# joystick-DAC-GPS.net
KiCad netlist of a schematic drawn in EAGLE
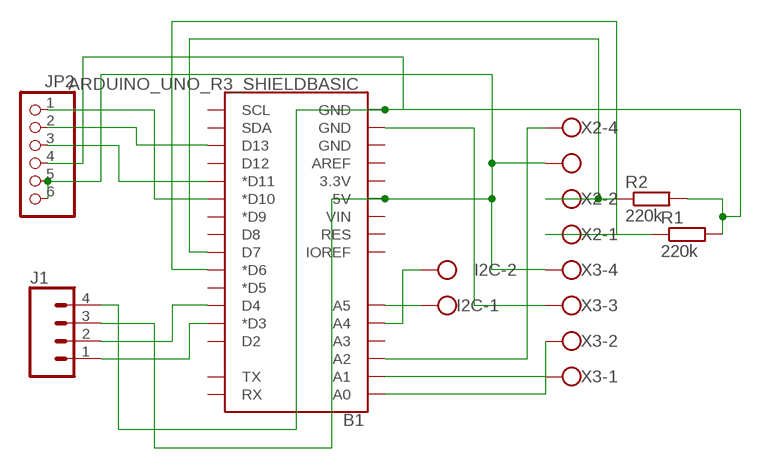
[diagram p0: schematic, sheet 1]

(export (version "E")
  (design (tool "Eeschema 10.0.6"))
  (components
    (comp (ref "B1")
      (value "ARDUINO_UNO_R3_SHIELDBASIC")
      (footprint "eagle-import:UNO_R3_SHIELD")
      (libsource (lib "eagle-import") (part "ARDUINO_UNO_R3_SHIELDBASIC"))
    )
    (comp (ref "I2C")
      (value "W237-102")
      (footprint "eagle-import:W237-102")
      (fields (field (name "MPN") "237-102"))
      (libsource (lib "eagle-import") (part "W237-102"))
    )
    (comp (ref "J1")
      (value "CONN_04")
      (footprint "eagle-import:1X04")
      (libsource (lib "eagle-import") (part "CONN_04"))
    )
    (comp (ref "JP2")
      (value "PINHD-1X6")
      (footprint "eagle-import:1X06")
      (libsource (lib "eagle-import") (part "PINHD-1X6"))
    )
    (comp (ref "R1")
      (value "220k")
      (footprint "eagle-import:0204_7")
      (libsource (lib "eagle-import") (part "R-EU_0204/7"))
    )
    (comp (ref "R2")
      (value "220k")
      (footprint "eagle-import:0204_7")
      (libsource (lib "eagle-import") (part "R-EU_0204/7"))
    )
    (comp (ref "X2")
      (value "W237-4")
      (footprint "eagle-import:W237-4")
      (libsource (lib "eagle-import") (part "W237-4"))
    )
    (comp (ref "X3")
      (value "W237-4")
      (footprint "eagle-import:W237-4")
      (libsource (lib "eagle-import") (part "W237-4"))
    )
  )
  (nets
    (net (code "1") (name "Net-(B1-*D3)") (class "Default")
      (node (ref "B1") (pin "D3") (pinfunction "*D3_D3") (pintype "bidirectional"))
      (node (ref "J1") (pin "1") (pinfunction "1_1") (pintype "passive"))
    )
    (net (code "2") (name "Net-(B1-*D6)") (class "Default")
      (node (ref "B1") (pin "D6") (pinfunction "*D6_D6") (pintype "bidirectional"))
      (node (ref "R1") (pin "1") (pinfunction "1_1") (pintype "passive"))
      (node (ref "X2") (pin "1") (pinfunction "KL_1") (pintype "passive"))
    )
    (net (code "3") (name "Net-(B1-*D10)") (class "Default")
      (node (ref "B1") (pin "D10") (pinfunction "*D10_D10") (pintype "bidirectional"))
      (node (ref "JP2") (pin "1") (pinfunction "1_1") (pintype "passive"))
    )
    (net (code "4") (name "Net-(B1-*D11)") (class "Default")
      (node (ref "B1") (pin "D11") (pinfunction "*D11_D11") (pintype "bidirectional"))
      (node (ref "JP2") (pin "3") (pinfunction "3_3") (pintype "passive"))
    )
    (net (code "5") (name "Net-(B1-GND-PadGND@0)") (class "Default")
      (node (ref "B1") (pin "GND@0") (pinfunction "GND_GND@0") (pintype "bidirectional"))
      (node (ref "J1") (pin "4") (pinfunction "4_4") (pintype "passive"))
      (node (ref "JP2") (pin "4") (pinfunction "4_4") (pintype "passive"))
      (node (ref "R1") (pin "2") (pinfunction "2_2") (pintype "passive"))
      (node (ref "R2") (pin "2") (pinfunction "2_2") (pintype "passive"))
    )
    (net (code "6") (name "Net-(B1-PadD4)") (class "Default")
      (node (ref "B1") (pin "D4") (pinfunction "D4_D4") (pintype "bidirectional"))
      (node (ref "J1") (pin "2") (pinfunction "2_2") (pintype "passive"))
    )
    (net (code "7") (name "Net-(B1-PadD13)") (class "Default")
      (node (ref "B1") (pin "D13") (pinfunction "D13_D13") (pintype "bidirectional"))
      (node (ref "JP2") (pin "2") (pinfunction "2_2") (pintype "passive"))
    )
    (net (code "8") (name "Net-(I2CA-KL)") (class "Default")
      (node (ref "B1") (pin "A5") (pinfunction "A5_A5") (pintype "bidirectional"))
      (node (ref "I2C") (pin "1") (pinfunction "KL_1") (pintype "passive"))
    )
    (net (code "9") (name "Net-(I2CB-KL)") (class "Default")
      (node (ref "B1") (pin "A4") (pinfunction "A4_A4") (pintype "bidirectional"))
      (node (ref "I2C") (pin "2") (pinfunction "KL_2") (pintype "passive"))
    )
    (net (code "10") (name "Net-(X2B-KL)") (class "Default")
      (node (ref "B1") (pin "D7") (pinfunction "D7_D7") (pintype "bidirectional"))
      (node (ref "R2") (pin "1") (pinfunction "1_1") (pintype "passive"))
      (node (ref "X2") (pin "2") (pinfunction "KL_2") (pintype "passive"))
    )
    (net (code "11") (name "Net-(X2C-KL)") (class "Default")
      (node (ref "B1") (pin "5V") (pinfunction "5V_5V") (pintype "bidirectional"))
      (node (ref "J1") (pin "3") (pinfunction "3_3") (pintype "passive"))
      (node (ref "JP2") (pin "5") (pinfunction "5_5") (pintype "passive"))
      (node (ref "JP2") (pin "6") (pinfunction "6_6") (pintype "passive"))
      (node (ref "X2") (pin "3") (pinfunction "KL_3") (pintype "passive"))
      (node (ref "X3") (pin "4") (pinfunction "KL_4") (pintype "passive"))
    )
    (net (code "12") (name "Net-(X2D-KL)") (class "Default")
      (node (ref "B1") (pin "A2") (pinfunction "A2_A2") (pintype "bidirectional"))
      (node (ref "X2") (pin "4") (pinfunction "KL_4") (pintype "passive"))
    )
    (net (code "13") (name "Net-(X3A-KL)") (class "Default")
      (node (ref "B1") (pin "A1") (pinfunction "A1_A1") (pintype "bidirectional"))
      (node (ref "X3") (pin "1") (pinfunction "KL_1") (pintype "passive"))
    )
    (net (code "14") (name "Net-(X3B-KL)") (class "Default")
      (node (ref "B1") (pin "A0") (pinfunction "A0_A0") (pintype "bidirectional"))
      (node (ref "X3") (pin "2") (pinfunction "KL_2") (pintype "passive"))
    )
    (net (code "15") (name "Net-(X3C-KL)") (class "Default")
      (node (ref "B1") (pin "GND@1") (pinfunction "GND_GND@1") (pintype "bidirectional"))
      (node (ref "X3") (pin "3") (pinfunction "KL_3") (pintype "passive"))
    )
    (net (code "16") (name "unconnected-(B1-*D5-PadD5)") (class "Default")
      (node (ref "B1") (pin "D5") (pinfunction "*D5_D5") (pintype "bidirectional"))
    )
    (net (code "17") (name "unconnected-(B1-*D9-PadD9)") (class "Default")
      (node (ref "B1") (pin "D9") (pinfunction "*D9_D9") (pintype "bidirectional"))
    )
    (net (code "18") (name "unconnected-(B1-GND-PadGND@2)") (class "Default")
      (node (ref "B1") (pin "GND@2") (pinfunction "GND_GND@2") (pintype "bidirectional"))
    )
    (net (code "19") (name "unconnected-(B1-Pad3.3V)") (class "Default")
      (node (ref "B1") (pin "3.3V") (pinfunction "3.3V_3.3V") (pintype "bidirectional"))
    )
    (net (code "20") (name "unconnected-(B1-PadA3)") (class "Default")
      (node (ref "B1") (pin "A3") (pinfunction "A3_A3") (pintype "bidirectional"))
    )
    (net (code "21") (name "unconnected-(B1-PadAREF)") (class "Default")
      (node (ref "B1") (pin "AREF") (pinfunction "AREF_AREF") (pintype "bidirectional"))
    )
    (net (code "22") (name "unconnected-(B1-PadD2)") (class "Default")
      (node (ref "B1") (pin "D2") (pinfunction "D2_D2") (pintype "bidirectional"))
    )
    (net (code "23") (name "unconnected-(B1-PadD8)") (class "Default")
      (node (ref "B1") (pin "D8") (pinfunction "D8_D8") (pintype "bidirectional"))
    )
    (net (code "24") (name "unconnected-(B1-PadD12)") (class "Default")
      (node (ref "B1") (pin "D12") (pinfunction "D12_D12") (pintype "bidirectional"))
    )
    (net (code "25") (name "unconnected-(B1-PadIOREF)") (class "Default")
      (node (ref "B1") (pin "IOREF") (pinfunction "IOREF_IOREF") (pintype "bidirectional"))
    )
    (net (code "26") (name "unconnected-(B1-PadRES)") (class "Default")
      (node (ref "B1") (pin "RES") (pinfunction "RES_RES") (pintype "bidirectional"))
    )
    (net (code "27") (name "unconnected-(B1-PadRX)") (class "Default")
      (node (ref "B1") (pin "RX") (pinfunction "RX_RX") (pintype "bidirectional"))
    )
    (net (code "28") (name "unconnected-(B1-PadSCL)") (class "Default")
      (node (ref "B1") (pin "SCL") (pinfunction "SCL_SCL") (pintype "bidirectional"))
    )
    (net (code "29") (name "unconnected-(B1-PadSDA)") (class "Default")
      (node (ref "B1") (pin "SDA") (pinfunction "SDA_SDA") (pintype "bidirectional"))
    )
    (net (code "30") (name "unconnected-(B1-PadTX)") (class "Default")
      (node (ref "B1") (pin "TX") (pinfunction "TX_TX") (pintype "bidirectional"))
    )
    (net (code "31") (name "unconnected-(B1-PadVIN)") (class "Default")
      (node (ref "B1") (pin "VIN") (pinfunction "VIN_VIN") (pintype "bidirectional"))
    )
  )
)
